# Drive_Y.net
KiCad netlist of a schematic drawn in Altium Designer
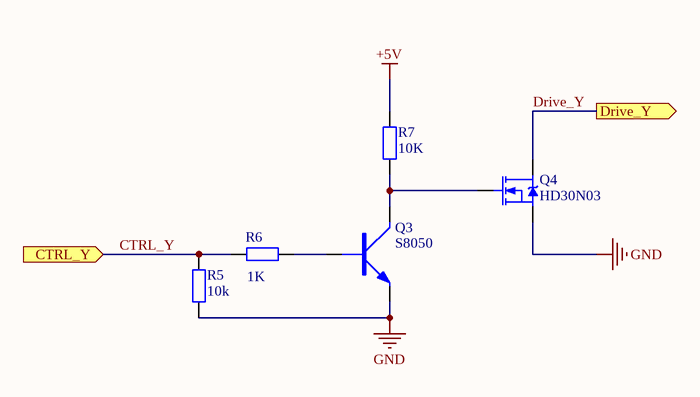
[diagram p0: Drive_Y.SchDoc]

(export (version "E")
  (design (tool "Eeschema 10.0.6"))
  (components
    (comp (ref "Q3")
      (value "S8050")
      (footprint "SOT-23")
      (description "NPN三极管")
      (libsource (lib "三极管") (part "NPN"))
    )
    (comp (ref "Q4")
      (value "HD30N03")
      (footprint "TO252")
      (description "N沟道场效应管")
      (libsource (lib "MOS管") (part "N-MOS"))
    )
    (comp (ref "R5")
      (value "10k")
      (footprint "R 0603")
      (description "贴片电阻")
      (fields (field (name "版权归属") "源创客"))
      (libsource (lib "源创客") (part "R"))
    )
    (comp (ref "R6")
      (value "1K")
      (footprint "R 0603")
      (description "贴片电阻")
      (fields (field (name "版权归属") "源创客"))
      (libsource (lib "源创客") (part "R"))
    )
    (comp (ref "R7")
      (value "10K")
      (footprint "R 0603")
      (description "贴片电阻")
      (fields (field (name "版权归属") "源创客"))
      (libsource (lib "源创客") (part "R"))
    )
  )
  (nets
    (net (code "1") (name "+5V") (class "Default")
      (node (ref "R7") (pin "2") (pinfunction "2_2") (pintype "passive"))
    )
    (net (code "2") (name "/CTRL_Y") (class "Default")
      (node (ref "R5") (pin "2") (pinfunction "2_2") (pintype "passive"))
      (node (ref "R6") (pin "1") (pinfunction "1_1") (pintype "passive"))
    )
    (net (code "3") (name "/Drive_Y") (class "Default")
      (node (ref "Q4") (pin "D") (pinfunction "D_D") (pintype "passive"))
    )
    (net (code "4") (name "GND") (class "Default")
      (node (ref "Q3") (pin "E") (pinfunction "E_E") (pintype "passive"))
      (node (ref "Q4") (pin "S") (pinfunction "S_S") (pintype "passive"))
      (node (ref "R5") (pin "1") (pinfunction "1_1") (pintype "passive"))
    )
    (net (code "5") (name "Net-(Q3-PadB)") (class "Default")
      (node (ref "Q3") (pin "B") (pinfunction "B_B") (pintype "passive"))
      (node (ref "R6") (pin "2") (pinfunction "2_2") (pintype "passive"))
    )
    (net (code "6") (name "Net-(Q3-PadC)") (class "Default")
      (node (ref "Q3") (pin "C") (pinfunction "C_C") (pintype "passive"))
      (node (ref "Q4") (pin "G") (pinfunction "G_G") (pintype "passive"))
      (node (ref "R7") (pin "1") (pinfunction "1_1") (pintype "passive"))
    )
  )
)
